# 04_-_PSU__5V_AUX.net
KiCad netlist of a schematic drawn in Altium Designer
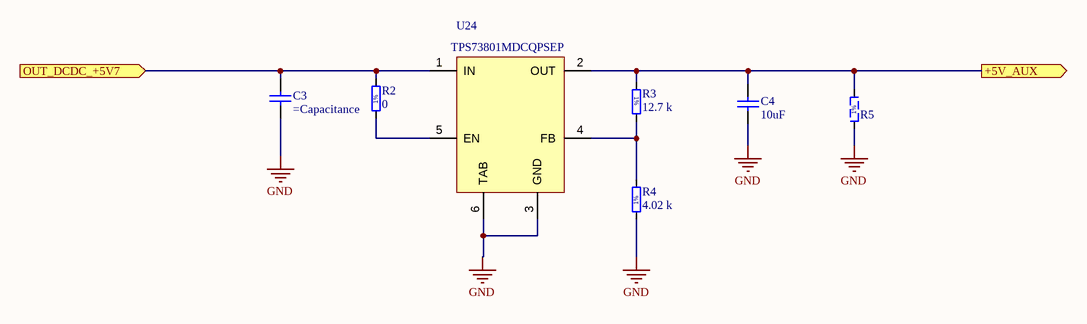
[diagram p0: [04] - PSU_+5V_AUX.SchDoc]

(export (version "E")
  (design (tool "Eeschema 10.0.6"))
  (components
    (comp (ref "C3")
      (value "~")
      (footprint "CAPC100X55X55L35N")
      (description "Multilayer Ceramic Capacitor, 0.022 uF, 25 V, ± 5%, X7R, 0402 [1005 Metric]")
      (fields
        (field (name "MANUFACTURER") "Murata")
        (field (name "MANUFACTURER PART NUMBER") "GRM155R71E223JA61D")
      )
      (libsource (lib "W_Passive") (part "GRM155R71E223JA61"))
    )
    (comp (ref "C4")
      (value "10uF")
      (footprint "CAPC320X160X180L55N")
      (description "CAP CER 10UF 50V X7R 1206")
      (fields
        (field (name "MANUFACTURER") "TDK")
        (field (name "MANUFACTURER PART NUMBER") "C3216X7R1H106K160AC")
      )
      (libsource (lib "W_Passive") (part "C3216X7R1H106K160AC"))
    )
    (comp (ref "R2")
      (value "0")
      (footprint "RESC100X50X40L25N")
      (description "RES 0 OHM 1/16W 1% 0402")
      (fields
        (field (name "MANUFACTURER") "Vishay")
        (field (name "MANUFACTURER PART NUMBER") "CRCW04020000Z0EDC")
      )
      (libsource (lib "W_Preferiti") (part "CRCW04020000Z0EDC"))
    )
    (comp (ref "R3")
      (value "12.7 k")
      (footprint "RESC100X50X40L25N")
      (description "RES 12K7 OHM 1/16W 1% 0402")
      (fields (field (name "TOLERANCE") "±1%") (field (name "MANUFACTURER") "Vishay Dale"))
      (libsource (lib "W_Passive") (part "CRCW040212K7FKED"))
    )
    (comp (ref "R4")
      (value "4.02 k")
      (footprint "RESC100X50X40L25N")
      (description "RES 4K02 OHM 1/16W 1% 0402")
      (fields (field (name "TOLERANCE") "±1%") (field (name "MANUFACTURER") "Vishay Dale"))
      (libsource (lib "W_Passive") (part "CRCW04024K02FKED"))
    )
    (comp (ref "R5")
      (value "NoBom")
      (footprint "RESC2012X60N")
      (description "Resistore Non in BOM")
      (libsource (lib "W_Passive") (part "1RES_NO_BOM_0805"))
    )
    (comp (ref "U24")
      (value "TPS73801MDCQPSEP")
      (footprint "SOT127P706X180-6N")
      (fields (field (name "MANUFACTURER") "Texas Instruments"))
      (libsource (lib "W_IC") (part "TPS73801MDCQPSEP"))
    )
  )
  (nets
    (net (code "1") (name "/+5V_AUX") (class "Default")
      (node (ref "C4") (pin "2") (pinfunction "2_2") (pintype "passive"))
      (node (ref "R3") (pin "1") (pinfunction "1_1") (pintype "passive"))
      (node (ref "R5") (pin "2") (pinfunction "2_2") (pintype "passive"))
      (node (ref "U24") (pin "2") (pinfunction "OUT_2") (pintype "passive"))
    )
    (net (code "2") (name "/OUT_DCDC_+5V7") (class "Default")
      (node (ref "C3") (pin "2") (pinfunction "2_2") (pintype "passive"))
      (node (ref "R2") (pin "2") (pinfunction "2_2") (pintype "passive"))
      (node (ref "U24") (pin "1") (pinfunction "IN_1") (pintype "passive"))
    )
    (net (code "3") (name "GND") (class "Default")
      (node (ref "C3") (pin "1") (pinfunction "1_1") (pintype "passive"))
      (node (ref "C4") (pin "1") (pinfunction "1_1") (pintype "passive"))
      (node (ref "R4") (pin "1") (pinfunction "1_1") (pintype "passive"))
      (node (ref "R5") (pin "1") (pinfunction "1_1") (pintype "passive"))
      (node (ref "U24") (pin "3") (pinfunction "GND_3") (pintype "passive"))
      (node (ref "U24") (pin "6") (pinfunction "TAB_6") (pintype "passive"))
    )
    (net (code "4") (name "Net-(U24-EN)") (class "Default")
      (node (ref "R2") (pin "1") (pinfunction "1_1") (pintype "passive"))
      (node (ref "U24") (pin "5") (pinfunction "EN_5") (pintype "passive"))
    )
    (net (code "5") (name "Net-(U24-FB)") (class "Default")
      (node (ref "R3") (pin "2") (pinfunction "2_2") (pintype "passive"))
      (node (ref "R4") (pin "2") (pinfunction "2_2") (pintype "passive"))
      (node (ref "U24") (pin "4") (pinfunction "FB_4") (pintype "passive"))
    )
  )
)
